# ZigBee.net
KiCad netlist of a schematic drawn in Altium Designer
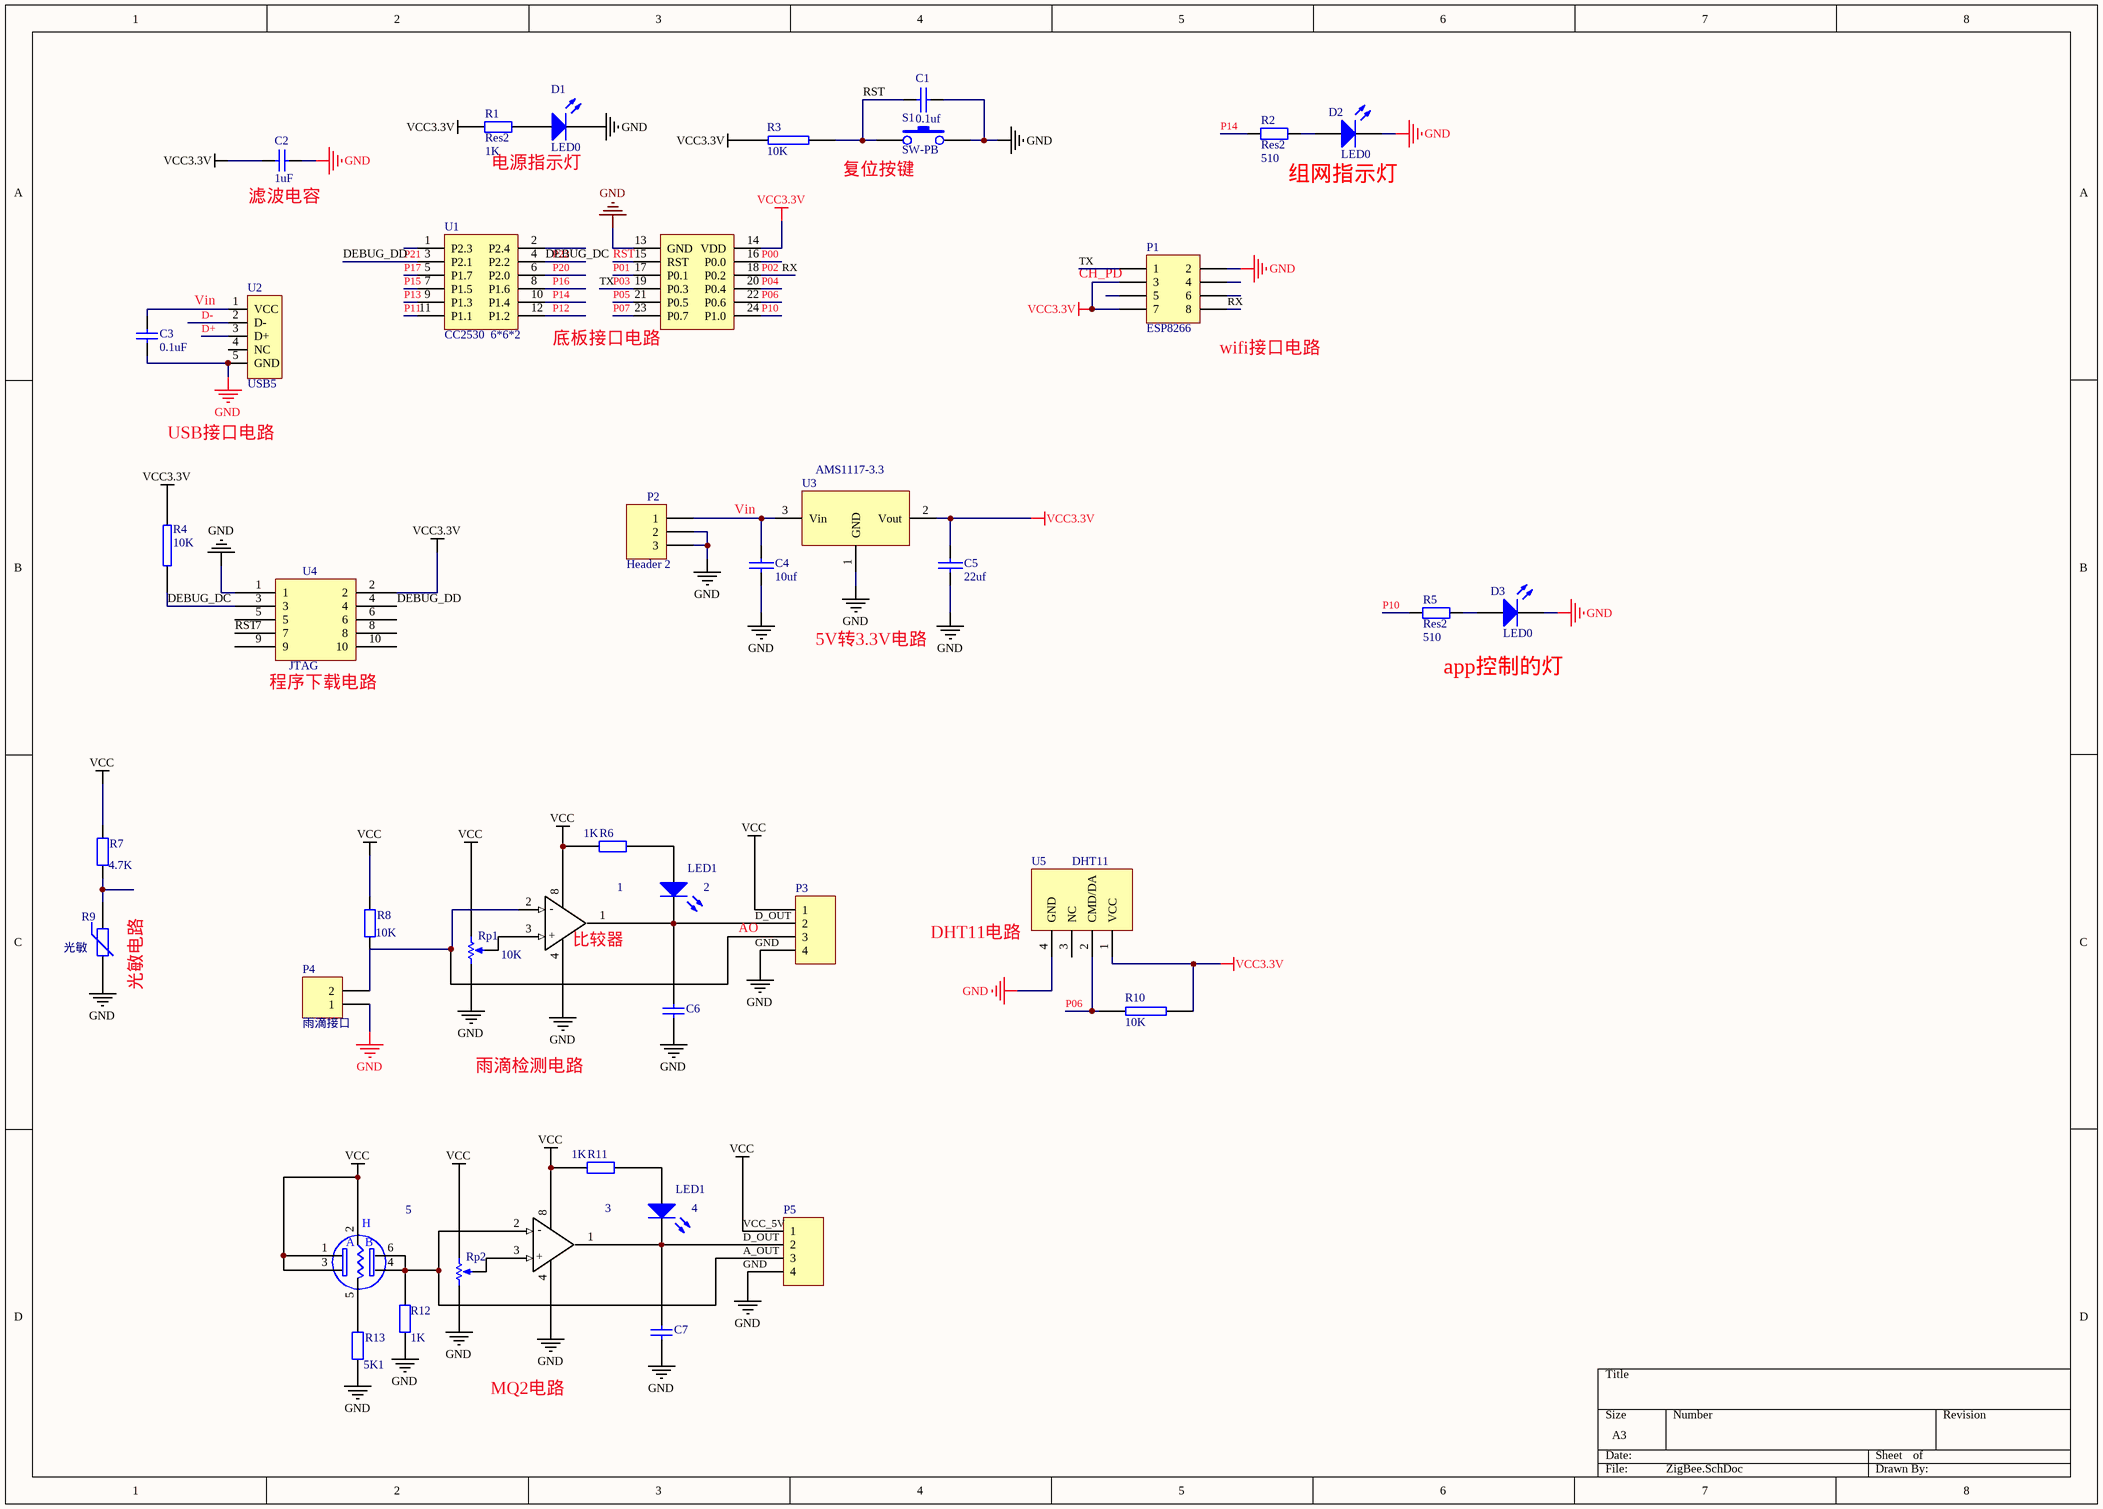
[diagram p0: ZigBee.SchDoc]

(export (version "E")
  (design (tool "Eeschema 10.0.6"))
  (components
    (comp (ref "1") (value "~") (libsource (lib "mysch") (part "bijiaoqi")))
    (comp (ref "2")
      (value "LED1")
      (footprint "LED-1")
      (description "Typical RED GaAs LED")
      (fields (field (name "PUBLISHER") "Altium Limited"))
      (libsource (lib "Miscellaneous Devices") (part "LED1"))
    )
    (comp (ref "3") (value "~") (libsource (lib "mysch") (part "bijiaoqi")))
    (comp (ref "4")
      (value "LED1")
      (footprint "LED-1")
      (description "Typical RED GaAs LED")
      (fields (field (name "PUBLISHER") "Altium Limited"))
      (libsource (lib "Miscellaneous Devices") (part "LED1"))
    )
    (comp (ref "5") (value "~") (libsource (lib "mysch") (part "MQ-2")))
    (comp (ref "C1")
      (value "0.1uf")
      (footprint "0805C")
      (description "Capacitor")
      (libsource (lib "*") (part "CAP"))
    )
    (comp (ref "C2")
      (value "1uF")
      (footprint "0805C")
      (description "Capacitor")
      (fields (field (name "PUBLISHER") "Altium Limited"))
      (libsource (lib "Miscellaneous Devices") (part "Cap"))
    )
    (comp (ref "C3")
      (value "0.1uF")
      (footprint "0805C")
      (description "Capacitor")
      (fields (field (name "PUBLISHER") "Altium Limited"))
      (libsource (lib "Miscellaneous Devices") (part "Cap"))
    )
    (comp (ref "C4")
      (value "10uf")
      (footprint "0805C")
      (description "Capacitor")
      (libsource (lib "*") (part "CAP"))
    )
    (comp (ref "C5")
      (value "22uf")
      (footprint "0805C")
      (description "Capacitor")
      (libsource (lib "*") (part "CAP"))
    )
    (comp (ref "C6")
      (value "~")
      (footprint "CAPC3216L")
      (description "Capacitor (Semiconductor SIM Model)")
      (fields (field (name "PUBLISHER") "Altium Limited"))
      (libsource (lib "Miscellaneous Devices") (part "Cap Semi"))
    )
    (comp (ref "C7")
      (value "~")
      (footprint "CAPC3216L")
      (description "Capacitor (Semiconductor SIM Model)")
      (fields (field (name "PUBLISHER") "Altium Limited"))
      (libsource (lib "Miscellaneous Devices") (part "Cap Semi"))
    )
    (comp (ref "D1")
      (value "LED0")
      (footprint "0805D")
      (description "Typical INFRARED GaAs LED")
      (fields (field (name "PUBLISHER") "Altium Limited"))
      (libsource (lib "Miscellaneous Devices") (part "LED0"))
    )
    (comp (ref "D2")
      (value "LED0")
      (footprint "0805D")
      (description "Typical INFRARED GaAs LED")
      (fields (field (name "PUBLISHER") "Altium Limited"))
      (libsource (lib "Miscellaneous Devices") (part "LED0"))
    )
    (comp (ref "D3")
      (value "LED0")
      (footprint "0805D")
      (description "Typical INFRARED GaAs LED")
      (fields (field (name "PUBLISHER") "Altium Limited"))
      (libsource (lib "Miscellaneous Devices") (part "LED0"))
    )
    (comp (ref "P1")
      (value "ESP8266")
      (footprint "HDR2X4")
      (description "Header, 4-Pin, Dual row")
      (fields (field (name "PUBLISHER") "Altium Limited"))
      (libsource (lib "Miscellaneous Connectors") (part "Header 4X2"))
    )
    (comp (ref "P2")
      (value "Header 2")
      (footprint "DC-SEAT")
      (description "Header, 3-Pin")
      (fields (field (name "PUBLISHER") "Altium Limited"))
      (libsource (lib "Miscellaneous Connectors") (part "Header 3"))
    )
    (comp (ref "P3")
      (value "~")
      (footprint "HDR1X4")
      (description "Header, 4-Pin")
      (fields (field (name "PUBLISHER") "Altium Limited"))
      (libsource (lib "Miscellaneous Connectors") (part "Header 4"))
    )
    (comp (ref "P4")
      (value "雨滴接口")
      (footprint "HDR1X2")
      (description "Header, 2-Pin")
      (fields (field (name "PUBLISHER") "Altium Limited"))
      (libsource (lib "Miscellaneous Connectors") (part "Header 2"))
    )
    (comp (ref "P5")
      (value "~")
      (footprint "HDR1X4")
      (description "Header, 4-Pin")
      (fields (field (name "PUBLISHER") "Altium Limited"))
      (libsource (lib "Miscellaneous Connectors") (part "Header 4"))
    )
    (comp (ref "R1")
      (value "Res2")
      (footprint "0805R")
      (description "Resistor")
      (fields (field (name "ALTIUM_VALUE") "1K") (field (name "PUBLISHER") "Altium Limited"))
      (libsource (lib "") (part "Res2_1"))
    )
    (comp (ref "R2")
      (value "Res2")
      (footprint "0805R")
      (description "Resistor")
      (fields (field (name "ALTIUM_VALUE") "510") (field (name "PUBLISHER") "Altium Limited"))
      (libsource (lib "") (part "Res2_1"))
    )
    (comp (ref "R3") (value "10K") (footprint "0805R") (libsource (lib "*") (part "RES2")))
    (comp (ref "R4") (value "10K") (footprint "0805R") (libsource (lib "*") (part "RES2")))
    (comp (ref "R5")
      (value "Res2")
      (footprint "0805R")
      (description "Resistor")
      (fields (field (name "ALTIUM_VALUE") "510") (field (name "PUBLISHER") "Altium Limited"))
      (libsource (lib "") (part "Res2_1"))
    )
    (comp (ref "R6")
      (value "1K")
      (footprint "AXIAL-0.4")
      (description "Resistor")
      (fields (field (name "PUBLISHER") "Altium Limited"))
      (libsource (lib "") (part "Res2_2"))
    )
    (comp (ref "R7")
      (value "4.7K")
      (footprint "AXIAL-0.4")
      (description "Resistor")
      (fields (field (name "PUBLISHER") "Altium Limited"))
      (libsource (lib "Miscellaneous Devices") (part "Res2"))
    )
    (comp (ref "R8")
      (value "10K")
      (footprint "AXIAL-0.4")
      (description "Resistor")
      (fields (field (name "PUBLISHER") "Altium Limited"))
      (libsource (lib "Miscellaneous Devices") (part "Res2"))
    )
    (comp (ref "R9")
      (value "光敏")
      (footprint "RESC2012N")
      (description "Varistor (Voltage-Sensitive Resistor)")
      (fields (field (name "PUBLISHER") "Altium Limited"))
      (libsource (lib "Miscellaneous Devices") (part "Res Varistor"))
    )
    (comp (ref "R10") (value "10K") (footprint "0805R") (libsource (lib "*") (part "RES2")))
    (comp (ref "R11")
      (value "1K")
      (footprint "AXIAL-0.4")
      (description "Resistor")
      (fields (field (name "PUBLISHER") "Altium Limited"))
      (libsource (lib "") (part "Res2_2"))
    )
    (comp (ref "R12")
      (value "1K")
      (footprint "AXIAL-0.4")
      (description "Resistor")
      (fields (field (name "PUBLISHER") "Altium Limited"))
      (libsource (lib "Miscellaneous Devices") (part "Res2"))
    )
    (comp (ref "R13")
      (value "5K1")
      (footprint "AXIAL-0.4")
      (description "Resistor")
      (fields (field (name "PUBLISHER") "Altium Limited"))
      (libsource (lib "Miscellaneous Devices") (part "Res2"))
    )
    (comp (ref "Rp1")
      (value "10K")
      (footprint "VR5")
      (description "Potentiometer")
      (fields (field (name "PUBLISHER") "Altium Limited"))
      (libsource (lib "Miscellaneous Devices") (part "RPot"))
    )
    (comp (ref "Rp2")
      (value "~")
      (footprint "VR5")
      (description "Potentiometer")
      (fields (field (name "PUBLISHER") "Altium Limited"))
      (libsource (lib "Miscellaneous Devices") (part "RPot"))
    )
    (comp (ref "S1") (value "SW-PB") (footprint "四脚按键") (libsource (lib "*") (part "SW-PB")))
    (comp (ref "U1")
      (value "CC2530  6*6*2")
      (footprint "CC2530  6*6*2")
      (libsource (lib "mysch") (part "CC2530  6*6*2"))
    )
    (comp (ref "U2") (value "USB5") (footprint "USB5") (libsource (lib "mysch") (part "USB5")))
    (comp (ref "U3") (value "AMS1117-3.3") (footprint "SOT-223") (libsource (lib "mysch") (part "AMS1117")))
    (comp (ref "U4") (value "JTAG") (footprint "JTAG") (libsource (lib "*") (part "JTAG")))
    (comp (ref "U5") (value "DHT11") (libsource (lib "mysch") (part "DHT11")))
  )
  (nets
    (net (code "1") (name "/AO") (class "Default")
      (node (ref "1") (pin "2") (pintype "input"))
      (node (ref "P3") (pin "3") (pinfunction "3_3") (pintype "passive"))
    )
    (net (code "2") (name "/A_OUT") (class "Default")
      (node (ref "3") (pin "2") (pintype "input"))
      (node (ref "5") (pin "4") (pintype "passive"))
      (node (ref "5") (pin "6") (pintype "passive"))
      (node (ref "P5") (pin "3") (pinfunction "3_3") (pintype "passive"))
      (node (ref "R12") (pin "2") (pinfunction "2_2") (pintype "passive"))
    )
    (net (code "4") (name "/D+") (class "Default")
      (node (ref "U2") (pin "3") (pinfunction "D+_3") (pintype "passive"))
    )
    (net (code "5") (name "/D-") (class "Default")
      (node (ref "U2") (pin "2") (pinfunction "D-_2") (pintype "passive"))
    )
    (net (code "6") (name "/DEBUG_DC") (class "Default")
      (node (ref "R4") (pin "1") (pinfunction "1_1") (pintype "passive"))
      (node (ref "U1") (pin "4") (pinfunction "P2.2_4") (pintype "passive"))
      (node (ref "U4") (pin "3") (pinfunction "3_3") (pintype "passive"))
    )
    (net (code "7") (name "/DEBUG_DD") (class "Default")
      (node (ref "U1") (pin "3") (pinfunction "P2.1_3") (pintype "passive"))
      (node (ref "U4") (pin "4") (pinfunction "4_4") (pintype "passive"))
    )
    (net (code "8") (name "/D_OUT") (class "Default")
      (node (ref "1") (pin "1") (pintype "passive"))
      (node (ref "2") (pin "2") (pinfunction "K_2") (pintype "passive"))
      (node (ref "3") (pin "1") (pintype "passive"))
      (node (ref "4") (pin "2") (pinfunction "K_2") (pintype "passive"))
      (node (ref "C6") (pin "1") (pinfunction "1_1") (pintype "passive"))
      (node (ref "C7") (pin "1") (pinfunction "1_1") (pintype "passive"))
      (node (ref "P3") (pin "2") (pinfunction "2_2") (pintype "passive"))
      (node (ref "P5") (pin "2") (pinfunction "2_2") (pintype "passive"))
    )
    (net (code "9") (name "/P00") (class "Default")
      (node (ref "U1") (pin "16") (pinfunction "P0.0_16") (pintype "passive"))
    )
    (net (code "10") (name "/P01") (class "Default")
      (node (ref "U1") (pin "17") (pinfunction "P0.1_17") (pintype "passive"))
    )
    (net (code "11") (name "/P02") (class "Default")
      (node (ref "P1") (pin "8") (pinfunction "8_8") (pintype "passive"))
      (node (ref "U1") (pin "18") (pinfunction "P0.2_18") (pintype "passive"))
    )
    (net (code "12") (name "/P03") (class "Default")
      (node (ref "P1") (pin "1") (pinfunction "1_1") (pintype "passive"))
      (node (ref "U1") (pin "19") (pinfunction "P0.3_19") (pintype "passive"))
    )
    (net (code "13") (name "/P04") (class "Default")
      (node (ref "U1") (pin "20") (pinfunction "P0.4_20") (pintype "passive"))
    )
    (net (code "14") (name "/P05") (class "Default")
      (node (ref "U1") (pin "21") (pinfunction "P0.5_21") (pintype "passive"))
    )
    (net (code "15") (name "/P06") (class "Default")
      (node (ref "R10") (pin "2") (pinfunction "2_2") (pintype "passive"))
      (node (ref "U1") (pin "22") (pinfunction "P0.6_22") (pintype "passive"))
      (node (ref "U5") (pin "2") (pinfunction "CMD/DA_2") (pintype "passive"))
    )
    (net (code "16") (name "/P07") (class "Default")
      (node (ref "U1") (pin "23") (pinfunction "P0.7_23") (pintype "passive"))
    )
    (net (code "17") (name "/P10") (class "Default")
      (node (ref "R5") (pin "1") (pinfunction "1_1") (pintype "passive"))
      (node (ref "U1") (pin "24") (pinfunction "P1.0_24") (pintype "passive"))
    )
    (net (code "18") (name "/P11") (class "Default")
      (node (ref "U1") (pin "11") (pinfunction "P1.1_11") (pintype "passive"))
    )
    (net (code "19") (name "/P12") (class "Default")
      (node (ref "U1") (pin "12") (pinfunction "P1.2_12") (pintype "passive"))
    )
    (net (code "20") (name "/P13") (class "Default")
      (node (ref "U1") (pin "9") (pinfunction "P1.3_9") (pintype "passive"))
    )
    (net (code "21") (name "/P14") (class "Default")
      (node (ref "R2") (pin "1") (pinfunction "1_1") (pintype "passive"))
      (node (ref "U1") (pin "10") (pinfunction "P1.4_10") (pintype "passive"))
    )
    (net (code "22") (name "/P15") (class "Default")
      (node (ref "U1") (pin "7") (pinfunction "P1.5_7") (pintype "passive"))
    )
    (net (code "23") (name "/P16") (class "Default")
      (node (ref "U1") (pin "8") (pinfunction "P1.6_8") (pintype "passive"))
    )
    (net (code "24") (name "/P17") (class "Default")
      (node (ref "U1") (pin "5") (pinfunction "P1.7_5") (pintype "passive"))
    )
    (net (code "25") (name "/P20") (class "Default")
      (node (ref "U1") (pin "6") (pinfunction "P2.0_6") (pintype "passive"))
    )
    (net (code "26") (name "/RST") (class "Default")
      (node (ref "C1") (pin "2") (pinfunction "2_2") (pintype "passive"))
      (node (ref "R3") (pin "1") (pinfunction "1_1") (pintype "passive"))
      (node (ref "S1") (pin "1") (pinfunction "1_1") (pintype "passive"))
      (node (ref "U1") (pin "15") (pinfunction "RST_15") (pintype "passive"))
      (node (ref "U4") (pin "7") (pinfunction "7_7") (pintype "passive"))
    )
    (net (code "27") (name "/Vin") (class "Default")
      (node (ref "C3") (pin "1") (pinfunction "1_1") (pintype "passive"))
      (node (ref "C4") (pin "1") (pinfunction "1_1") (pintype "passive"))
      (node (ref "P2") (pin "1") (pinfunction "1_1") (pintype "passive"))
      (node (ref "U2") (pin "1") (pinfunction "VCC_1") (pintype "passive"))
      (node (ref "U3") (pin "3") (pinfunction "Vin_3") (pintype "passive"))
    )
    (net (code "28") (name "GND") (class "Default")
      (node (ref "1") (pin "4") (pintype "passive"))
      (node (ref "3") (pin "4") (pintype "passive"))
      (node (ref "C1") (pin "1") (pinfunction "1_1") (pintype "passive"))
      (node (ref "C2") (pin "1") (pinfunction "1_1") (pintype "passive"))
      (node (ref "C3") (pin "2") (pinfunction "2_2") (pintype "passive"))
      (node (ref "C4") (pin "2") (pinfunction "2_2") (pintype "passive"))
      (node (ref "C5") (pin "2") (pinfunction "2_2") (pintype "passive"))
      (node (ref "C6") (pin "2") (pinfunction "2_2") (pintype "passive"))
      (node (ref "C7") (pin "2") (pinfunction "2_2") (pintype "passive"))
      (node (ref "D1") (pin "K") (pinfunction "K_K") (pintype "passive"))
      (node (ref "D2") (pin "K") (pinfunction "K_K") (pintype "passive"))
      (node (ref "D3") (pin "K") (pinfunction "K_K") (pintype "passive"))
      (node (ref "P1") (pin "2") (pinfunction "2_2") (pintype "passive"))
      (node (ref "P2") (pin "2") (pinfunction "2_2") (pintype "passive"))
      (node (ref "P2") (pin "3") (pinfunction "3_3") (pintype "passive"))
      (node (ref "P3") (pin "4") (pinfunction "4_4") (pintype "passive"))
      (node (ref "P4") (pin "1") (pinfunction "1_1") (pintype "passive"))
      (node (ref "P5") (pin "4") (pinfunction "4_4") (pintype "passive"))
      (node (ref "R12") (pin "1") (pinfunction "1_1") (pintype "passive"))
      (node (ref "R13") (pin "1") (pinfunction "1_1") (pintype "passive"))
      (node (ref "Rp1") (pin "1") (pinfunction "TOP_1") (pintype "passive"))
      (node (ref "Rp2") (pin "1") (pinfunction "TOP_1") (pintype "passive"))
      (node (ref "S1") (pin "2") (pinfunction "2_2") (pintype "passive"))
      (node (ref "U1") (pin "13") (pinfunction "GND_13") (pintype "passive"))
      (node (ref "U2") (pin "5") (pinfunction "GND_5") (pintype "passive"))
      (node (ref "U3") (pin "1") (pinfunction "GND_1") (pintype "passive"))
      (node (ref "U4") (pin "1") (pinfunction "1_1") (pintype "passive"))
      (node (ref "U5") (pin "4") (pinfunction "GND_4") (pintype "passive"))
    )
    (net (code "29") (name "Net-(2-A)") (class "Default")
      (node (ref "2") (pin "1") (pinfunction "A_1") (pintype "passive"))
      (node (ref "R6") (pin "1") (pinfunction "1_1") (pintype "passive"))
    )
    (net (code "30") (name "Net-(4-A)") (class "Default")
      (node (ref "4") (pin "1") (pinfunction "A_1") (pintype "passive"))
      (node (ref "R11") (pin "1") (pinfunction "1_1") (pintype "passive"))
    )
    (net (code "31") (name "Net-(5-Pad5)") (class "Default")
      (node (ref "5") (pin "5") (pintype "passive"))
      (node (ref "R13") (pin "2") (pinfunction "2_2") (pintype "passive"))
    )
    (net (code "32") (name "Net-(D1-PadA)") (class "Default")
      (node (ref "D1") (pin "A") (pinfunction "A_A") (pintype "passive"))
      (node (ref "R1") (pin "2") (pinfunction "2_2") (pintype "passive"))
    )
    (net (code "33") (name "Net-(D2-PadA)") (class "Default")
      (node (ref "D2") (pin "A") (pinfunction "A_A") (pintype "passive"))
      (node (ref "R2") (pin "2") (pinfunction "2_2") (pintype "passive"))
    )
    (net (code "34") (name "Net-(D3-PadA)") (class "Default")
      (node (ref "D3") (pin "A") (pinfunction "A_A") (pintype "passive"))
      (node (ref "R5") (pin "2") (pinfunction "2_2") (pintype "passive"))
    )
    (net (code "35") (name "Net-(P4-Pad2)") (class "Default")
      (node (ref "P4") (pin "2") (pinfunction "2_2") (pintype "passive"))
      (node (ref "R8") (pin "1") (pinfunction "1_1") (pintype "passive"))
    )
    (net (code "36") (name "Net-(R7-Pad1)") (class "Default")
      (node (ref "R7") (pin "1") (pinfunction "1_1") (pintype "passive"))
      (node (ref "R9") (pin "1") (pinfunction "1_1") (pintype "passive"))
    )
    (net (code "37") (name "Net-(Rp1-TAP)") (class "Default")
      (node (ref "1") (pin "3") (pintype "input"))
      (node (ref "Rp1") (pin "3") (pinfunction "TAP_3") (pintype "passive"))
    )
    (net (code "38") (name "Net-(Rp2-TAP)") (class "Default")
      (node (ref "3") (pin "3") (pintype "input"))
      (node (ref "Rp2") (pin "3") (pinfunction "TAP_3") (pintype "passive"))
    )
    (net (code "39") (name "VCC") (class "Default")
      (node (ref "1") (pin "8") (pintype "passive"))
      (node (ref "3") (pin "8") (pintype "passive"))
      (node (ref "5") (pin "1") (pintype "passive"))
      (node (ref "5") (pin "2") (pintype "passive"))
      (node (ref "5") (pin "3") (pintype "passive"))
      (node (ref "P3") (pin "1") (pinfunction "1_1") (pintype "passive"))
      (node (ref "P5") (pin "1") (pinfunction "1_1") (pintype "passive"))
      (node (ref "R11") (pin "2") (pinfunction "2_2") (pintype "passive"))
      (node (ref "R6") (pin "2") (pinfunction "2_2") (pintype "passive"))
      (node (ref "R7") (pin "2") (pinfunction "2_2") (pintype "passive"))
      (node (ref "R8") (pin "2") (pinfunction "2_2") (pintype "passive"))
      (node (ref "Rp1") (pin "2") (pinfunction "BOT_2") (pintype "passive"))
      (node (ref "Rp2") (pin "2") (pinfunction "BOT_2") (pintype "passive"))
    )
    (net (code "40") (name "VCC3.3V") (class "Default")
      (node (ref "C2") (pin "2") (pinfunction "2_2") (pintype "passive"))
      (node (ref "C5") (pin "1") (pinfunction "1_1") (pintype "passive"))
      (node (ref "P1") (pin "3") (pinfunction "3_3") (pintype "passive"))
      (node (ref "P1") (pin "7") (pinfunction "7_7") (pintype "passive"))
      (node (ref "R1") (pin "1") (pinfunction "1_1") (pintype "passive"))
      (node (ref "R10") (pin "1") (pinfunction "1_1") (pintype "passive"))
      (node (ref "R3") (pin "2") (pinfunction "2_2") (pintype "passive"))
      (node (ref "R4") (pin "2") (pinfunction "2_2") (pintype "passive"))
      (node (ref "U1") (pin "14") (pinfunction "VDD_14") (pintype "passive"))
      (node (ref "U3") (pin "2") (pinfunction "Vout_2") (pintype "passive"))
      (node (ref "U4") (pin "2") (pinfunction "2_2") (pintype "passive"))
      (node (ref "U5") (pin "1") (pinfunction "VCC_1") (pintype "passive"))
    )
    (net (code "41") (name "unconnected-(P1-Pad4)") (class "Default")
      (node (ref "P1") (pin "4") (pinfunction "4_4") (pintype "passive"))
    )
    (net (code "42") (name "unconnected-(P1-Pad5)") (class "Default")
      (node (ref "P1") (pin "5") (pinfunction "5_5") (pintype "passive"))
    )
    (net (code "43") (name "unconnected-(P1-Pad6)") (class "Default")
      (node (ref "P1") (pin "6") (pinfunction "6_6") (pintype "passive"))
    )
    (net (code "44") (name "unconnected-(R9-Pad2)") (class "Default")
      (node (ref "R9") (pin "2") (pinfunction "2_2") (pintype "passive"))
    )
    (net (code "45") (name "unconnected-(U1-P2.3-Pad1)") (class "Default")
      (node (ref "U1") (pin "1") (pinfunction "P2.3_1") (pintype "passive"))
    )
    (net (code "46") (name "unconnected-(U1-P2.4-Pad2)") (class "Default")
      (node (ref "U1") (pin "2") (pinfunction "P2.4_2") (pintype "passive"))
    )
    (net (code "47") (name "unconnected-(U2-NC-Pad4)") (class "Default")
      (node (ref "U2") (pin "4") (pinfunction "NC_4") (pintype "passive"))
    )
    (net (code "48") (name "unconnected-(U4-Pad5)") (class "Default")
      (node (ref "U4") (pin "5") (pinfunction "5_5") (pintype "passive"))
    )
    (net (code "49") (name "unconnected-(U4-Pad6)") (class "Default")
      (node (ref "U4") (pin "6") (pinfunction "6_6") (pintype "passive"))
    )
    (net (code "50") (name "unconnected-(U4-Pad8)") (class "Default")
      (node (ref "U4") (pin "8") (pinfunction "8_8") (pintype "passive"))
    )
    (net (code "51") (name "unconnected-(U4-Pad9)") (class "Default")
      (node (ref "U4") (pin "9") (pinfunction "9_9") (pintype "passive"))
    )
    (net (code "52") (name "unconnected-(U4-Pad10)") (class "Default")
      (node (ref "U4") (pin "10") (pinfunction "10_10") (pintype "passive"))
    )
    (net (code "53") (name "unconnected-(U5-NC-Pad3)") (class "Default")
      (node (ref "U5") (pin "3") (pinfunction "NC_3") (pintype "passive"))
    )
  )
)
